# Power.net
KiCad netlist of a schematic drawn in Altium Designer
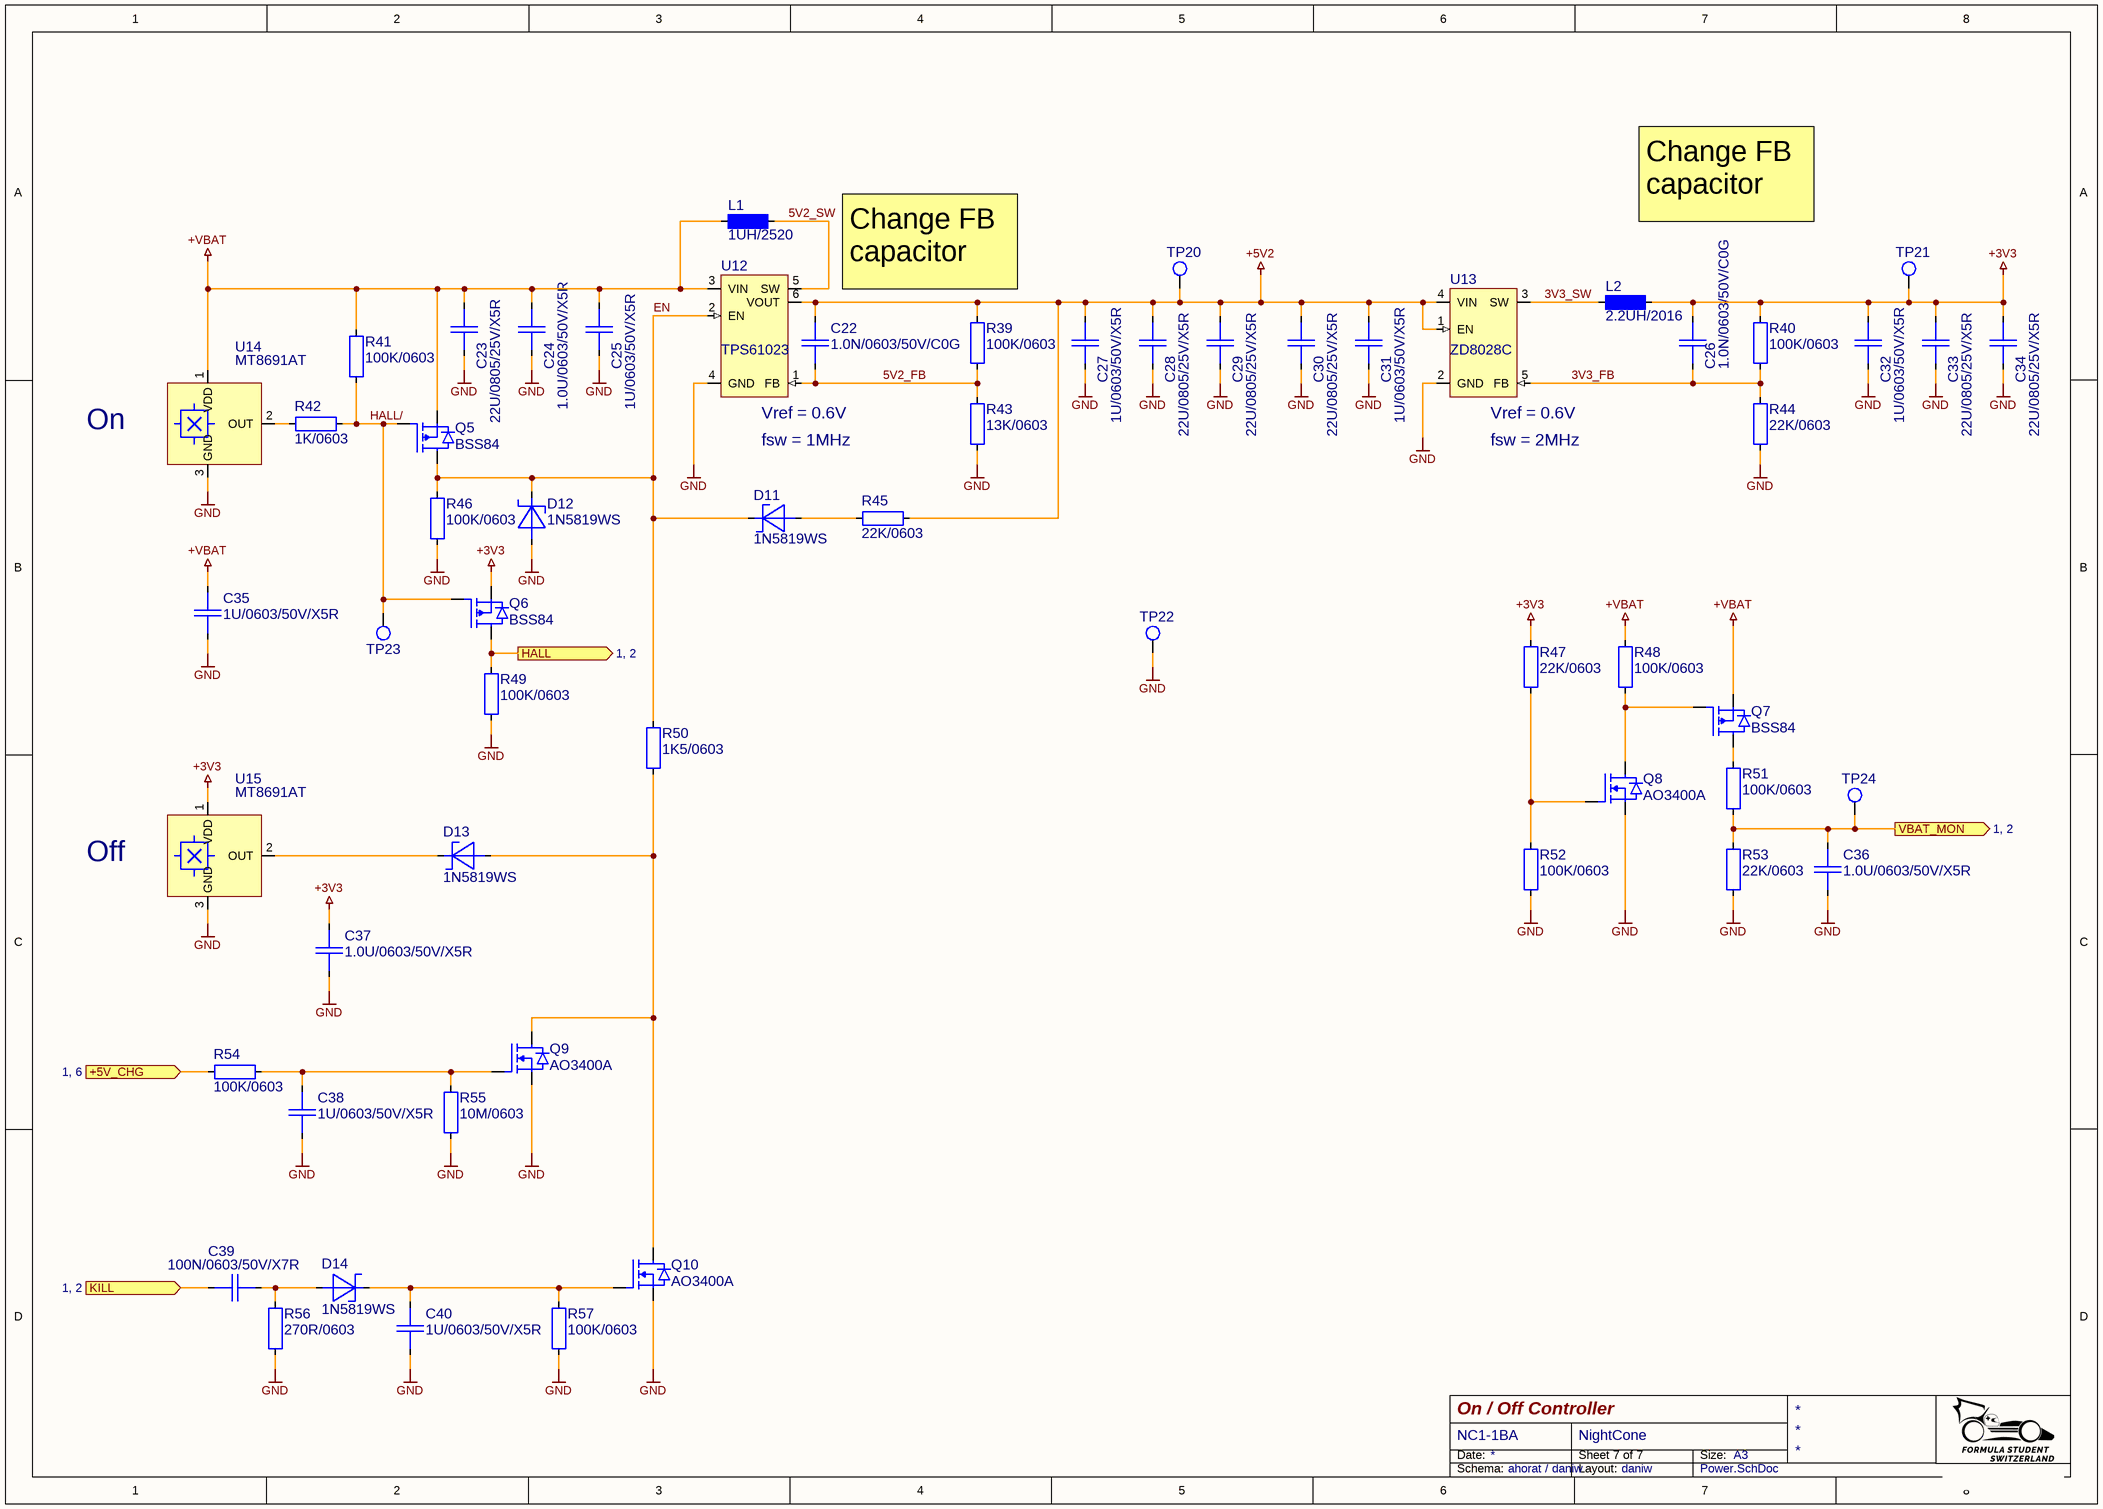
[diagram p0: Power.SchDoc]

(export (version "E")
  (design (tool "Eeschema 10.0.6"))
  (components
    (comp (ref "C22")
      (value "1.0N/0603/50V/C0G")
      (footprint "CAP0603_C0G")
      (description "CAP SM 0603 1.0nF 50V C0G")
      (fields (field (name "MANUFACTURER") "GENERIC"))
      (libsource (lib "daniw_altium_lib") (part "C"))
    )
    (comp (ref "C23")
      (value "22U/0805/25V/X5R")
      (footprint "CAP0805_X7R")
      (description "CAP SM 0805 22uF 25V X5R")
      (fields (field (name "MANUFACTURER") "GENERIC"))
      (libsource (lib "daniw_altium_lib") (part "C"))
    )
    (comp (ref "C24")
      (value "1.0U/0603/50V/X5R")
      (footprint "CAP0603_X7R")
      (description "CAP SM 0603 1.0uF 50V X5R")
      (fields (field (name "MANUFACTURER") "GENERIC"))
      (libsource (lib "daniw_altium_lib") (part "C"))
    )
    (comp (ref "C25")
      (value "1U/0603/50V/X5R")
      (footprint "CAP0603_X7R")
      (description "CAP SM 0603 1.0uF 50V X5R")
      (fields (field (name "MANUFACTURER") "GENERIC"))
      (libsource (lib "daniw_altium_lib") (part "C"))
    )
    (comp (ref "C26")
      (value "1.0N/0603/50V/C0G")
      (footprint "CAP0603_C0G")
      (description "CAP SM 0603 1.0nF 50V C0G")
      (fields (field (name "MANUFACTURER") "GENERIC"))
      (libsource (lib "daniw_altium_lib") (part "C"))
    )
    (comp (ref "C27")
      (value "1U/0603/50V/X5R")
      (footprint "CAP0603_X7R")
      (description "CAP SM 0603 1.0uF 50V X5R")
      (fields (field (name "MANUFACTURER") "GENERIC"))
      (libsource (lib "daniw_altium_lib") (part "C"))
    )
    (comp (ref "C28")
      (value "22U/0805/25V/X5R")
      (footprint "CAP0805_X7R")
      (description "CAP SM 0805 22uF 25V X5R")
      (fields (field (name "MANUFACTURER") "GENERIC"))
      (libsource (lib "daniw_altium_lib") (part "C"))
    )
    (comp (ref "C29")
      (value "22U/0805/25V/X5R")
      (footprint "CAP0805_X7R")
      (description "CAP SM 0805 22uF 25V X5R")
      (fields (field (name "MANUFACTURER") "GENERIC"))
      (libsource (lib "daniw_altium_lib") (part "C"))
    )
    (comp (ref "C30")
      (value "22U/0805/25V/X5R")
      (footprint "CAP0805_X7R")
      (description "CAP SM 0805 22uF 25V X5R")
      (fields (field (name "MANUFACTURER") "GENERIC"))
      (libsource (lib "daniw_altium_lib") (part "C"))
    )
    (comp (ref "C31")
      (value "1U/0603/50V/X5R")
      (footprint "CAP0603_X7R")
      (description "CAP SM 0603 1.0uF 50V X5R")
      (fields (field (name "MANUFACTURER") "GENERIC"))
      (libsource (lib "daniw_altium_lib") (part "C"))
    )
    (comp (ref "C32")
      (value "1U/0603/50V/X5R")
      (footprint "CAP0603_X7R")
      (description "CAP SM 0603 1.0uF 50V X5R")
      (fields (field (name "MANUFACTURER") "GENERIC"))
      (libsource (lib "daniw_altium_lib") (part "C"))
    )
    (comp (ref "C33")
      (value "22U/0805/25V/X5R")
      (footprint "CAP0805_X7R")
      (description "CAP SM 0805 22uF 25V X5R")
      (fields (field (name "MANUFACTURER") "GENERIC"))
      (libsource (lib "daniw_altium_lib") (part "C"))
    )
    (comp (ref "C34")
      (value "22U/0805/25V/X5R")
      (footprint "CAP0805_X7R")
      (description "CAP SM 0805 22uF 25V X5R")
      (fields (field (name "MANUFACTURER") "GENERIC"))
      (libsource (lib "daniw_altium_lib") (part "C"))
    )
    (comp (ref "C35")
      (value "1U/0603/50V/X5R")
      (footprint "CAP0603_X7R")
      (description "CAP SM 0603 1.0uF 50V X5R")
      (fields (field (name "MANUFACTURER") "GENERIC"))
      (libsource (lib "daniw_altium_lib") (part "C"))
    )
    (comp (ref "C36")
      (value "1.0U/0603/50V/X5R")
      (footprint "CAP0603_X7R")
      (description "CAP SM 0603 1.0uF 50V X5R")
      (fields (field (name "MANUFACTURER") "GENERIC"))
      (libsource (lib "daniw_altium_lib") (part "C"))
    )
    (comp (ref "C37")
      (value "1.0U/0603/50V/X5R")
      (footprint "CAP0603_X7R")
      (description "CAP SM 0603 1.0uF 50V X5R")
      (fields (field (name "MANUFACTURER") "GENERIC"))
      (libsource (lib "daniw_altium_lib") (part "C"))
    )
    (comp (ref "C38")
      (value "1U/0603/50V/X5R")
      (footprint "CAP0603_X7R")
      (description "CAP SM 0603 1.0uF 50V X5R")
      (fields (field (name "MANUFACTURER") "GENERIC"))
      (libsource (lib "daniw_altium_lib") (part "C"))
    )
    (comp (ref "C39")
      (value "100N/0603/50V/X7R")
      (footprint "CAP0603_X7R")
      (description "CAP SM 0603 100nF 50V X7R")
      (fields (field (name "MANUFACTURER") "GENERIC"))
      (libsource (lib "daniw_altium_lib") (part "C"))
    )
    (comp (ref "C40")
      (value "1U/0603/50V/X5R")
      (footprint "CAP0603_X7R")
      (description "CAP SM 0603 1.0uF 50V X5R")
      (fields (field (name "MANUFACTURER") "GENERIC"))
      (libsource (lib "daniw_altium_lib") (part "C"))
    )
    (comp (ref "D11")
      (value "1N5819WS")
      (footprint "SOD2513X100")
      (description "40V 600mV@1A 1A SOD-323 Schottky Barrier Diodes (SBD) ROHS")
      (fields (field (name "MANUFACTURER") "GENERIC"))
      (libsource (lib "daniw_altium_lib") (part "D_Schottky"))
    )
    (comp (ref "D12")
      (value "1N5819WS")
      (footprint "SOD2513X100")
      (description "40V 600mV@1A 1A SOD-323 Schottky Barrier Diodes (SBD) ROHS")
      (fields (field (name "MANUFACTURER") "GENERIC"))
      (libsource (lib "daniw_altium_lib") (part "D_Schottky"))
    )
    (comp (ref "D13")
      (value "1N5819WS")
      (footprint "SOD2513X100")
      (description "40V 600mV@1A 1A SOD-323 Schottky Barrier Diodes (SBD) ROHS")
      (fields (field (name "MANUFACTURER") "GENERIC"))
      (libsource (lib "daniw_altium_lib") (part "D_Schottky"))
    )
    (comp (ref "D14")
      (value "1N5819WS")
      (footprint "SOD2513X100")
      (description "40V 600mV@1A 1A SOD-323 Schottky Barrier Diodes (SBD) ROHS")
      (fields (field (name "MANUFACTURER") "GENERIC"))
      (libsource (lib "daniw_altium_lib") (part "D_Schottky"))
    )
    (comp (ref "L1")
      (value "1UH/2520")
      (footprint "INDM2520X10")
      (description "1UH 2520 Shielded Inductor SMD")
      (fields (field (name "MANUFACTURER") "GENERIC"))
      (libsource (lib "daniw_altium_lib") (part "L"))
    )
    (comp (ref "L2")
      (value "2.2UH/2016")
      (footprint "INDM2016X10")
      (description "2.2UH 2016 Shielded Inductor SMD")
      (fields (field (name "MANUFACTURER") "GENERIC"))
      (libsource (lib "daniw_altium_lib") (part "L"))
    )
    (comp (ref "Q5")
      (value "BSS84")
      (footprint "SOT2395P280X125-3-SE")
      (description "50V P-Channel MOSFET")
      (fields (field (name "MANUFACTURER") "GENERIC"))
      (libsource (lib "daniw_altium_lib") (part "MOSFET P_SOT23"))
    )
    (comp (ref "Q6")
      (value "BSS84")
      (footprint "SOT2395P280X125-3-SE")
      (description "50V P-Channel MOSFET")
      (fields (field (name "MANUFACTURER") "GENERIC"))
      (libsource (lib "daniw_altium_lib") (part "MOSFET P_SOT23"))
    )
    (comp (ref "Q7")
      (value "BSS84")
      (footprint "SOT2395P280X125-3-SE")
      (description "50V P-Channel MOSFET")
      (fields (field (name "MANUFACTURER") "GENERIC"))
      (libsource (lib "daniw_altium_lib") (part "MOSFET P_SOT23"))
    )
    (comp (ref "Q8")
      (value "AO3400A")
      (footprint "SOT2395P280X125-3-SE")
      (description "30V N-Channel MOSFET")
      (fields (field (name "MANUFACTURER") "Alpha & Omega Semiconductor"))
      (libsource (lib "daniw_altium_lib") (part "MOSFET N_SOT23"))
    )
    (comp (ref "Q9")
      (value "AO3400A")
      (footprint "SOT2395P280X125-3-SE")
      (description "30V N-Channel MOSFET")
      (fields (field (name "MANUFACTURER") "Alpha & Omega Semiconductor"))
      (libsource (lib "daniw_altium_lib") (part "MOSFET N_SOT23"))
    )
    (comp (ref "Q10")
      (value "AO3400A")
      (footprint "SOT2395P280X125-3-SE")
      (description "30V N-Channel MOSFET")
      (fields (field (name "MANUFACTURER") "Alpha & Omega Semiconductor"))
      (libsource (lib "daniw_altium_lib") (part "MOSFET N_SOT23"))
    )
    (comp (ref "R39")
      (value "100K/0603")
      (footprint "R0603-0.40-WW")
      (description "RES SM 0603 100K")
      (fields (field (name "MANUFACTURER") "GENERIC"))
      (libsource (lib "daniw_altium_lib") (part "R"))
    )
    (comp (ref "R40")
      (value "100K/0603")
      (footprint "R0603-0.40-WW")
      (description "RES SM 0603 100K")
      (fields (field (name "MANUFACTURER") "GENERIC"))
      (libsource (lib "daniw_altium_lib") (part "R"))
    )
    (comp (ref "R41")
      (value "100K/0603")
      (footprint "R0603-0.40-WW")
      (description "RES SM 0603 100K")
      (fields (field (name "MANUFACTURER") "GENERIC"))
      (libsource (lib "daniw_altium_lib") (part "R"))
    )
    (comp (ref "R42")
      (value "1K/0603")
      (footprint "R0603-0.40-WW")
      (description "RES SM 0603 1K")
      (fields (field (name "MANUFACTURER") "GENERIC"))
      (libsource (lib "daniw_altium_lib") (part "R"))
    )
    (comp (ref "R43")
      (value "13K/0603")
      (footprint "R0603-0.40-WW")
      (description "RES SM 0603 13K")
      (fields (field (name "MANUFACTURER") "GENERIC"))
      (libsource (lib "daniw_altium_lib") (part "R"))
    )
    (comp (ref "R44")
      (value "22K/0603")
      (footprint "R0603-0.40-WW")
      (description "RES SM 0603 22K")
      (fields (field (name "MANUFACTURER") "GENERIC"))
      (libsource (lib "daniw_altium_lib") (part "R"))
    )
    (comp (ref "R45")
      (value "22K/0603")
      (footprint "R0603-0.40-WW")
      (description "RES SM 0603 22K")
      (fields (field (name "MANUFACTURER") "GENERIC"))
      (libsource (lib "daniw_altium_lib") (part "R"))
    )
    (comp (ref "R46")
      (value "100K/0603")
      (footprint "R0603-0.40-WW")
      (description "RES SM 0603 100K")
      (fields (field (name "MANUFACTURER") "GENERIC"))
      (libsource (lib "daniw_altium_lib") (part "R"))
    )
    (comp (ref "R47")
      (value "22K/0603")
      (footprint "R0603-0.40-WW")
      (description "RES SM 0603 22K")
      (fields (field (name "MANUFACTURER") "GENERIC"))
      (libsource (lib "daniw_altium_lib") (part "R"))
    )
    (comp (ref "R48")
      (value "100K/0603")
      (footprint "R0603-0.40-WW")
      (description "RES SM 0603 100K")
      (fields (field (name "MANUFACTURER") "GENERIC"))
      (libsource (lib "daniw_altium_lib") (part "R"))
    )
    (comp (ref "R49")
      (value "100K/0603")
      (footprint "R0603-0.40-WW")
      (description "RES SM 0603 100K")
      (fields (field (name "MANUFACTURER") "GENERIC"))
      (libsource (lib "daniw_altium_lib") (part "R"))
    )
    (comp (ref "R50")
      (value "1K5/0603")
      (footprint "R0603-0.40-WW")
      (description "RES SM 0603 1K5")
      (fields (field (name "MANUFACTURER") "GENERIC"))
      (libsource (lib "daniw_altium_lib") (part "R"))
    )
    (comp (ref "R51")
      (value "100K/0603")
      (footprint "R0603-0.40-WW")
      (description "RES SM 0603 100K")
      (fields (field (name "MANUFACTURER") "GENERIC"))
      (libsource (lib "daniw_altium_lib") (part "R"))
    )
    (comp (ref "R52")
      (value "100K/0603")
      (footprint "R0603-0.40-WW")
      (description "RES SM 0603 100K")
      (fields (field (name "MANUFACTURER") "GENERIC"))
      (libsource (lib "daniw_altium_lib") (part "R"))
    )
    (comp (ref "R53")
      (value "22K/0603")
      (footprint "R0603-0.40-WW")
      (description "RES SM 0603 22K")
      (fields (field (name "MANUFACTURER") "GENERIC"))
      (libsource (lib "daniw_altium_lib") (part "R"))
    )
    (comp (ref "R54")
      (value "100K/0603")
      (footprint "R0603-0.40-WW")
      (description "RES SM 0603 100K")
      (fields (field (name "MANUFACTURER") "GENERIC"))
      (libsource (lib "daniw_altium_lib") (part "R"))
    )
    (comp (ref "R55")
      (value "10M/0603")
      (footprint "R0603-0.40-WW")
      (description "RES SM 0603 10M")
      (fields (field (name "MANUFACTURER") "GENERIC"))
      (libsource (lib "daniw_altium_lib") (part "R"))
    )
    (comp (ref "R56")
      (value "270R/0603")
      (footprint "R0603-0.40-WW")
      (description "RES SM 0603 270R")
      (fields (field (name "MANUFACTURER") "GENERIC"))
      (libsource (lib "daniw_altium_lib") (part "R"))
    )
    (comp (ref "R57")
      (value "100K/0603")
      (footprint "R0603-0.40-WW")
      (description "RES SM 0603 100K")
      (fields (field (name "MANUFACTURER") "GENERIC"))
      (libsource (lib "daniw_altium_lib") (part "R"))
    )
    (comp (ref "TP20")
      (value "TP_THD_1.5/0.8")
      (footprint "TP_THD_1.5/0.8")
      (description "THT Test Point 1.5/0.8mm")
      (fields (field (name "MANUFACTURER") "NONE"))
      (libsource (lib "daniw_altium_lib") (part "Testpoint"))
    )
    (comp (ref "TP21")
      (value "TP_THD_1.5/0.8")
      (footprint "TP_THD_1.5/0.8")
      (description "THT Test Point 1.5/0.8mm")
      (fields (field (name "MANUFACTURER") "NONE"))
      (libsource (lib "daniw_altium_lib") (part "Testpoint"))
    )
    (comp (ref "TP22")
      (value "TP_THD_1.5/0.8")
      (footprint "TP_THD_1.5/0.8")
      (description "THT Test Point 1.5/0.8mm")
      (fields (field (name "MANUFACTURER") "NONE"))
      (libsource (lib "daniw_altium_lib") (part "Testpoint"))
    )
    (comp (ref "TP23")
      (value "TP_THD_1.5/0.8")
      (footprint "TP_THD_1.5/0.8")
      (description "THT Test Point 1.5/0.8mm")
      (fields (field (name "MANUFACTURER") "NONE"))
      (libsource (lib "daniw_altium_lib") (part "Testpoint"))
    )
    (comp (ref "TP24")
      (value "TP_THD_1.5/0.8")
      (footprint "TP_THD_1.5/0.8")
      (description "THT Test Point 1.5/0.8mm")
      (fields (field (name "MANUFACTURER") "NONE"))
      (libsource (lib "daniw_altium_lib") (part "Testpoint"))
    )
    (comp (ref "U12")
      (value "TPS61023")
      (footprint "SOT50P160X60-6-SE")
      (description "3.7-A Boost Converter with 0.5-V Ultra-low Input Voltage")
      (fields (field (name "MANUFACTURER") "Texas Instruments"))
      (libsource (lib "daniw_altium_lib") (part "TPS61023"))
    )
    (comp (ref "U13")
      (value "ZD8028C")
      (footprint "SOT2395P280X125-5-SW")
      (description "1.5A 2MHz 5.5V Synchronous Buck Converter")
      (fields (field (name "MANUFACTURER") "Zetta"))
      (libsource (lib "daniw_altium_lib") (part "ZD8028C"))
    )
    (comp (ref "U14")
      (value "MT8691AT")
      (footprint "SOT2395P280X125-3-SE")
      (description "MT8691AT Uni-polar, Nano Power Hall-Effect Switch IC")
      (fields (field (name "MANUFACTURER") "Magn Tek"))
      (libsource (lib "daniw_altium_lib") (part "UHE4913"))
    )
    (comp (ref "U15")
      (value "MT8691AT")
      (footprint "SOT2395P280X125-3-SE")
      (description "MT8691AT Uni-polar, Nano Power Hall-Effect Switch IC")
      (fields (field (name "MANUFACTURER") "Magn Tek"))
      (libsource (lib "daniw_altium_lib") (part "UHE4913"))
    )
  )
  (nets
    (net (code "1") (name "+3V3") (class "Default")
      (node (ref "C26") (pin "1") (pinfunction "1_1") (pintype "passive"))
      (node (ref "C32") (pin "2") (pinfunction "2_2") (pintype "passive"))
      (node (ref "C33") (pin "1") (pinfunction "1_1") (pintype "passive"))
      (node (ref "C34") (pin "1") (pinfunction "1_1") (pintype "passive"))
      (node (ref "C37") (pin "1") (pinfunction "1_1") (pintype "passive"))
      (node (ref "L2") (pin "2") (pinfunction "2_2") (pintype "passive"))
      (node (ref "Q6") (pin "2") (pinfunction "SOURCE_2") (pintype "passive"))
      (node (ref "R40") (pin "1") (pinfunction "1_1") (pintype "passive"))
      (node (ref "R47") (pin "1") (pinfunction "1_1") (pintype "passive"))
      (node (ref "TP21") (pin "1") (pinfunction "1_1") (pintype "passive"))
      (node (ref "U15") (pin "1") (pinfunction "VDD_1") (pintype "passive"))
    )
    (net (code "2") (name "+5V2") (class "Default")
      (node (ref "C22") (pin "1") (pinfunction "1_1") (pintype "passive"))
      (node (ref "C27") (pin "2") (pinfunction "2_2") (pintype "passive"))
      (node (ref "C28") (pin "1") (pinfunction "1_1") (pintype "passive"))
      (node (ref "C29") (pin "1") (pinfunction "1_1") (pintype "passive"))
      (node (ref "C30") (pin "1") (pinfunction "1_1") (pintype "passive"))
      (node (ref "C31") (pin "2") (pinfunction "2_2") (pintype "passive"))
      (node (ref "R39") (pin "1") (pinfunction "1_1") (pintype "passive"))
      (node (ref "R45") (pin "2") (pinfunction "2_2") (pintype "passive"))
      (node (ref "TP20") (pin "1") (pinfunction "1_1") (pintype "passive"))
      (node (ref "U12") (pin "6") (pinfunction "VOUT_6") (pintype "passive"))
      (node (ref "U13") (pin "1") (pinfunction "EN_1") (pintype "input"))
      (node (ref "U13") (pin "4") (pinfunction "VIN_4") (pintype "passive"))
    )
    (net (code "3") (name "+VBAT") (class "Default")
      (node (ref "C23") (pin "1") (pinfunction "1_1") (pintype "passive"))
      (node (ref "C24") (pin "2") (pinfunction "2_2") (pintype "passive"))
      (node (ref "C25") (pin "2") (pinfunction "2_2") (pintype "passive"))
      (node (ref "C35") (pin "1") (pinfunction "1_1") (pintype "passive"))
      (node (ref "L1") (pin "1") (pinfunction "1_1") (pintype "passive"))
      (node (ref "Q5") (pin "2") (pinfunction "SOURCE_2") (pintype "passive"))
      (node (ref "Q7") (pin "2") (pinfunction "SOURCE_2") (pintype "passive"))
      (node (ref "R41") (pin "1") (pinfunction "1_1") (pintype "passive"))
      (node (ref "R48") (pin "1") (pinfunction "1_1") (pintype "passive"))
      (node (ref "U12") (pin "3") (pinfunction "VIN_3") (pintype "passive"))
      (node (ref "U14") (pin "1") (pinfunction "VDD_1") (pintype "passive"))
    )
    (net (code "4") (name "/+5V_CHG") (class "Default")
      (node (ref "R54") (pin "1") (pinfunction "1_1") (pintype "passive"))
    )
    (net (code "5") (name "/3V3_FB") (class "Default")
      (node (ref "C26") (pin "2") (pinfunction "2_2") (pintype "passive"))
      (node (ref "R40") (pin "2") (pinfunction "2_2") (pintype "passive"))
      (node (ref "R44") (pin "1") (pinfunction "1_1") (pintype "passive"))
      (node (ref "U13") (pin "5") (pinfunction "FB_5") (pintype "input"))
    )
    (net (code "6") (name "/3V3_SW") (class "Default")
      (node (ref "L2") (pin "1") (pinfunction "1_1") (pintype "passive"))
      (node (ref "U13") (pin "3") (pinfunction "SW_3") (pintype "passive"))
    )
    (net (code "7") (name "/5V2_FB") (class "Default")
      (node (ref "C22") (pin "2") (pinfunction "2_2") (pintype "passive"))
      (node (ref "R39") (pin "2") (pinfunction "2_2") (pintype "passive"))
      (node (ref "R43") (pin "2") (pinfunction "2_2") (pintype "passive"))
      (node (ref "U12") (pin "1") (pinfunction "FB_1") (pintype "input"))
    )
    (net (code "8") (name "/5V2_SW") (class "Default")
      (node (ref "L1") (pin "2") (pinfunction "2_2") (pintype "passive"))
      (node (ref "U12") (pin "5") (pinfunction "SW_5") (pintype "passive"))
    )
    (net (code "9") (name "/EN") (class "Default")
      (node (ref "D11") (pin "1") (pinfunction "1_1") (pintype "passive"))
      (node (ref "D12") (pin "1") (pinfunction "1_1") (pintype "passive"))
      (node (ref "Q5") (pin "3") (pinfunction "DRAIN_3") (pintype "passive"))
      (node (ref "R46") (pin "1") (pinfunction "1_1") (pintype "passive"))
      (node (ref "R50") (pin "1") (pinfunction "1_1") (pintype "passive"))
      (node (ref "U12") (pin "2") (pinfunction "EN_2") (pintype "input"))
    )
    (net (code "10") (name "/HALL") (class "Default")
      (node (ref "Q6") (pin "3") (pinfunction "DRAIN_3") (pintype "passive"))
      (node (ref "R49") (pin "1") (pinfunction "1_1") (pintype "passive"))
    )
    (net (code "11") (name "/HALL{slash}") (class "Default")
      (node (ref "Q5") (pin "1") (pinfunction "GATE_1") (pintype "passive"))
      (node (ref "Q6") (pin "1") (pinfunction "GATE_1") (pintype "passive"))
      (node (ref "R41") (pin "2") (pinfunction "2_2") (pintype "passive"))
      (node (ref "R42") (pin "2") (pinfunction "2_2") (pintype "passive"))
      (node (ref "TP23") (pin "1") (pinfunction "1_1") (pintype "passive"))
    )
    (net (code "12") (name "/KILL") (class "Default")
      (node (ref "C39") (pin "1") (pinfunction "1_1") (pintype "passive"))
    )
    (net (code "13") (name "/VBAT_MON") (class "Default")
      (node (ref "C36") (pin "1") (pinfunction "1_1") (pintype "passive"))
      (node (ref "R51") (pin "2") (pinfunction "2_2") (pintype "passive"))
      (node (ref "R53") (pin "1") (pinfunction "1_1") (pintype "passive"))
      (node (ref "TP24") (pin "1") (pinfunction "1_1") (pintype "passive"))
    )
    (net (code "14") (name "GND") (class "Default")
      (node (ref "C23") (pin "2") (pinfunction "2_2") (pintype "passive"))
      (node (ref "C24") (pin "1") (pinfunction "1_1") (pintype "passive"))
      (node (ref "C25") (pin "1") (pinfunction "1_1") (pintype "passive"))
      (node (ref "C27") (pin "1") (pinfunction "1_1") (pintype "passive"))
      (node (ref "C28") (pin "2") (pinfunction "2_2") (pintype "passive"))
      (node (ref "C29") (pin "2") (pinfunction "2_2") (pintype "passive"))
      (node (ref "C30") (pin "2") (pinfunction "2_2") (pintype "passive"))
      (node (ref "C31") (pin "1") (pinfunction "1_1") (pintype "passive"))
      (node (ref "C32") (pin "1") (pinfunction "1_1") (pintype "passive"))
      (node (ref "C33") (pin "2") (pinfunction "2_2") (pintype "passive"))
      (node (ref "C34") (pin "2") (pinfunction "2_2") (pintype "passive"))
      (node (ref "C35") (pin "2") (pinfunction "2_2") (pintype "passive"))
      (node (ref "C36") (pin "2") (pinfunction "2_2") (pintype "passive"))
      (node (ref "C37") (pin "2") (pinfunction "2_2") (pintype "passive"))
      (node (ref "C38") (pin "2") (pinfunction "2_2") (pintype "passive"))
      (node (ref "C40") (pin "2") (pinfunction "2_2") (pintype "passive"))
      (node (ref "D12") (pin "2") (pinfunction "2_2") (pintype "passive"))
      (node (ref "Q10") (pin "2") (pinfunction "SOURCE_2") (pintype "passive"))
      (node (ref "Q8") (pin "2") (pinfunction "SOURCE_2") (pintype "passive"))
      (node (ref "Q9") (pin "2") (pinfunction "SOURCE_2") (pintype "passive"))
      (node (ref "R43") (pin "1") (pinfunction "1_1") (pintype "passive"))
      (node (ref "R44") (pin "2") (pinfunction "2_2") (pintype "passive"))
      (node (ref "R46") (pin "2") (pinfunction "2_2") (pintype "passive"))
      (node (ref "R49") (pin "2") (pinfunction "2_2") (pintype "passive"))
      (node (ref "R52") (pin "2") (pinfunction "2_2") (pintype "passive"))
      (node (ref "R53") (pin "2") (pinfunction "2_2") (pintype "passive"))
      (node (ref "R55") (pin "2") (pinfunction "2_2") (pintype "passive"))
      (node (ref "R56") (pin "2") (pinfunction "2_2") (pintype "passive"))
      (node (ref "R57") (pin "2") (pinfunction "2_2") (pintype "passive"))
      (node (ref "TP22") (pin "1") (pinfunction "1_1") (pintype "passive"))
      (node (ref "U12") (pin "4") (pinfunction "GND_4") (pintype "passive"))
      (node (ref "U13") (pin "2") (pinfunction "GND_2") (pintype "passive"))
      (node (ref "U14") (pin "3") (pinfunction "GND_3") (pintype "passive"))
      (node (ref "U15") (pin "3") (pinfunction "GND_3") (pintype "passive"))
    )
    (net (code "15") (name "Net-(C39-Pad2)") (class "Default")
      (node (ref "C39") (pin "2") (pinfunction "2_2") (pintype "passive"))
      (node (ref "D14") (pin "2") (pinfunction "2_2") (pintype "passive"))
      (node (ref "R56") (pin "1") (pinfunction "1_1") (pintype "passive"))
    )
    (net (code "16") (name "Net-(D11-Pad2)") (class "Default")
      (node (ref "D11") (pin "2") (pinfunction "2_2") (pintype "passive"))
      (node (ref "R45") (pin "1") (pinfunction "1_1") (pintype "passive"))
    )
    (net (code "17") (name "Net-(Q7-DRAIN)") (class "Default")
      (node (ref "Q7") (pin "3") (pinfunction "DRAIN_3") (pintype "passive"))
      (node (ref "R51") (pin "1") (pinfunction "1_1") (pintype "passive"))
    )
    (net (code "18") (name "Net-(Q7-GATE)") (class "Default")
      (node (ref "Q7") (pin "1") (pinfunction "GATE_1") (pintype "passive"))
      (node (ref "Q8") (pin "3") (pinfunction "DRAIN_3") (pintype "passive"))
      (node (ref "R48") (pin "2") (pinfunction "2_2") (pintype "passive"))
    )
    (net (code "19") (name "Net-(Q8-GATE)") (class "Default")
      (node (ref "Q8") (pin "1") (pinfunction "GATE_1") (pintype "passive"))
      (node (ref "R47") (pin "2") (pinfunction "2_2") (pintype "passive"))
      (node (ref "R52") (pin "1") (pinfunction "1_1") (pintype "passive"))
    )
    (net (code "20") (name "Net-(Q9-GATE)") (class "Default")
      (node (ref "C38") (pin "1") (pinfunction "1_1") (pintype "passive"))
      (node (ref "Q9") (pin "1") (pinfunction "GATE_1") (pintype "passive"))
      (node (ref "R54") (pin "2") (pinfunction "2_2") (pintype "passive"))
      (node (ref "R55") (pin "1") (pinfunction "1_1") (pintype "passive"))
    )
    (net (code "21") (name "Net-(Q10-DRAIN)") (class "Default")
      (node (ref "D13") (pin "2") (pinfunction "2_2") (pintype "passive"))
      (node (ref "Q10") (pin "3") (pinfunction "DRAIN_3") (pintype "passive"))
      (node (ref "Q9") (pin "3") (pinfunction "DRAIN_3") (pintype "passive"))
      (node (ref "R50") (pin "2") (pinfunction "2_2") (pintype "passive"))
    )
    (net (code "22") (name "Net-(Q10-GATE)") (class "Default")
      (node (ref "C40") (pin "1") (pinfunction "1_1") (pintype "passive"))
      (node (ref "D14") (pin "1") (pinfunction "1_1") (pintype "passive"))
      (node (ref "Q10") (pin "1") (pinfunction "GATE_1") (pintype "passive"))
      (node (ref "R57") (pin "1") (pinfunction "1_1") (pintype "passive"))
    )
    (net (code "23") (name "Net-(U14-OUT)") (class "Default")
      (node (ref "R42") (pin "1") (pinfunction "1_1") (pintype "passive"))
      (node (ref "U14") (pin "2") (pinfunction "OUT_2") (pintype "open_collector"))
    )
    (net (code "24") (name "Net-(U15-OUT)") (class "Default")
      (node (ref "D13") (pin "1") (pinfunction "1_1") (pintype "passive"))
      (node (ref "U15") (pin "2") (pinfunction "OUT_2") (pintype "open_collector"))
    )
  )
)
